# 10_-_POWER.net
KiCad netlist of a schematic drawn in Altium Designer
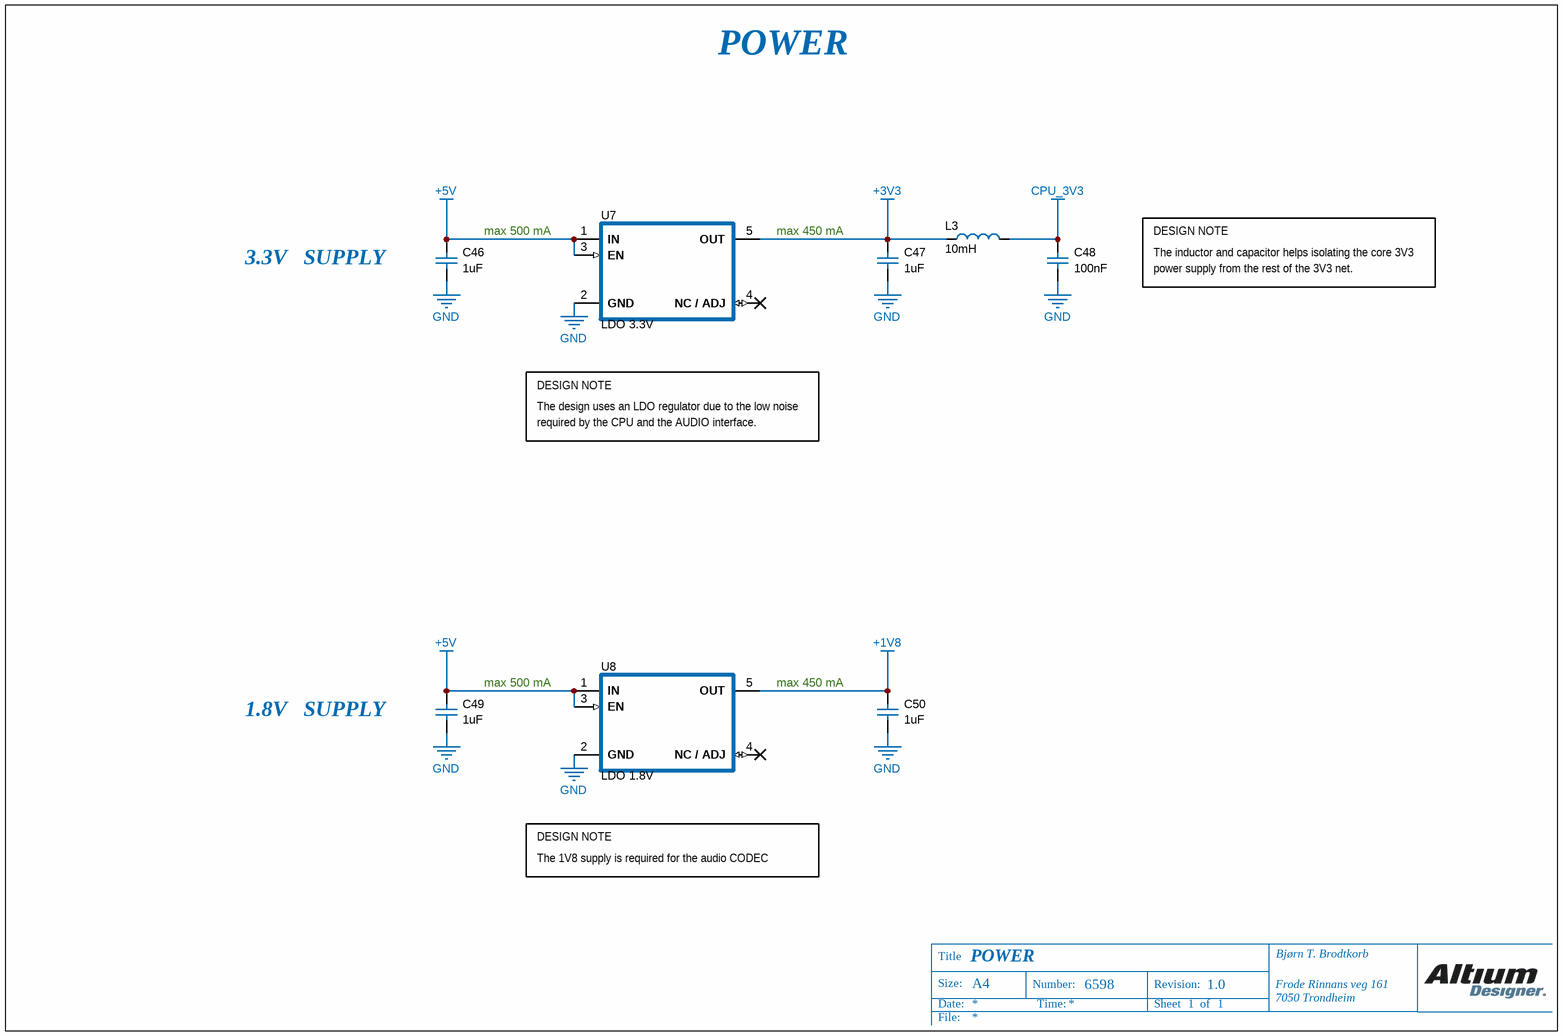
[diagram p0: [10] - POWER.SchDoc]

(export (version "E")
  (design (tool "Eeschema 10.0.6"))
  (components
    (comp (ref "C46")
      (value "1uF")
      (footprint "C0805")
      (description "C0805")
      (fields (field (name "Comment") "08053C105KAT2A"))
      (libsource (lib "Passive components") (part "08053C105KAT2A"))
    )
    (comp (ref "C47")
      (value "1uF")
      (footprint "C0805")
      (description "C0805")
      (fields (field (name "Comment") "08053C105KAT2A"))
      (libsource (lib "Passive components") (part "08053C105KAT2A"))
    )
    (comp (ref "C48")
      (value "100nF")
      (footprint "C0603")
      (description "C0603")
      (fields (field (name "Comment") "02016D104KAT2A"))
      (libsource (lib "Passive components") (part "02016D104KAT2A"))
    )
    (comp (ref "C49")
      (value "1uF")
      (footprint "C0805")
      (description "C0805")
      (fields (field (name "Comment") "08053C105KAT2A"))
      (libsource (lib "Passive components") (part "08053C105KAT2A"))
    )
    (comp (ref "C50")
      (value "1uF")
      (footprint "C0805")
      (description "C0805")
      (fields (field (name "Comment") "08053C105KAT2A"))
      (libsource (lib "Passive components") (part "08053C105KAT2A"))
    )
    (comp (ref "L3")
      (value "10mH")
      (footprint "Inductor 0603")
      (description "Inductor 0603")
      (fields (field (name "Comment") "MLZ1608A2R2WT"))
      (libsource (lib "Passive components") (part "MLZ1608A2R2WT"))
    )
    (comp (ref "U7")
      (value "LDO 3.3V")
      (footprint "NCV8161BSN330T1G")
      (description "LDO fixed 3.3V 450mA ultra-low noise")
      (libsource (lib "Voltage regulators") (part "NCV8161BSN330T1G"))
    )
    (comp (ref "U8")
      (value "LDO 1.8V")
      (footprint "SOT95P275X110-5N")
      (description "LDO fixed 1.8V 450mA ultra-low noise")
      (libsource (lib "Voltage regulators") (part "NCV8161ASN180T1G"))
    )
  )
  (nets
    (net (code "1") (name "+1V8") (class "Default")
      (node (ref "C50") (pin "2") (pinfunction "2_2") (pintype "passive"))
      (node (ref "U8") (pin "5") (pinfunction "OUT_5") (pintype "power_in"))
    )
    (net (code "2") (name "+3V3") (class "Default")
      (node (ref "C47") (pin "2") (pinfunction "2_2") (pintype "passive"))
      (node (ref "L3") (pin "1") (pinfunction "1_1") (pintype "passive"))
      (node (ref "U7") (pin "5") (pinfunction "OUT_5") (pintype "power_in"))
    )
    (net (code "3") (name "+5V") (class "Default")
      (node (ref "C46") (pin "2") (pinfunction "2_2") (pintype "passive"))
      (node (ref "C49") (pin "2") (pinfunction "2_2") (pintype "passive"))
      (node (ref "U7") (pin "1") (pinfunction "IN_1") (pintype "power_in"))
      (node (ref "U7") (pin "3") (pinfunction "EN_3") (pintype "input"))
      (node (ref "U8") (pin "1") (pinfunction "IN_1") (pintype "power_in"))
      (node (ref "U8") (pin "3") (pinfunction "EN_3") (pintype "input"))
    )
    (net (code "4") (name "CPU_3V3") (class "Default")
      (node (ref "C48") (pin "2") (pinfunction "2_2") (pintype "passive"))
      (node (ref "L3") (pin "2") (pinfunction "2_2") (pintype "passive"))
    )
    (net (code "5") (name "GND") (class "Default")
      (node (ref "C46") (pin "1") (pinfunction "1_1") (pintype "passive"))
      (node (ref "C47") (pin "1") (pinfunction "1_1") (pintype "passive"))
      (node (ref "C48") (pin "1") (pinfunction "1_1") (pintype "passive"))
      (node (ref "C49") (pin "1") (pinfunction "1_1") (pintype "passive"))
      (node (ref "C50") (pin "1") (pinfunction "1_1") (pintype "passive"))
      (node (ref "U7") (pin "2") (pinfunction "GND_2") (pintype "power_in"))
      (node (ref "U8") (pin "2") (pinfunction "GND_2") (pintype "power_in"))
    )
    (net (code "6") (name "unconnected-(U7-NC_{slash}_ADJ-Pad4)") (class "Default")
      (node (ref "U7") (pin "4") (pinfunction "NC_/_ADJ_4") (pintype "bidirectional+no_connect"))
    )
    (net (code "7") (name "unconnected-(U8-NC_{slash}_ADJ-Pad4)") (class "Default")
      (node (ref "U8") (pin "4") (pinfunction "NC_/_ADJ_4") (pintype "bidirectional+no_connect"))
    )
  )
)
